# Sense.net
KiCad netlist of a schematic drawn in Altium Designer
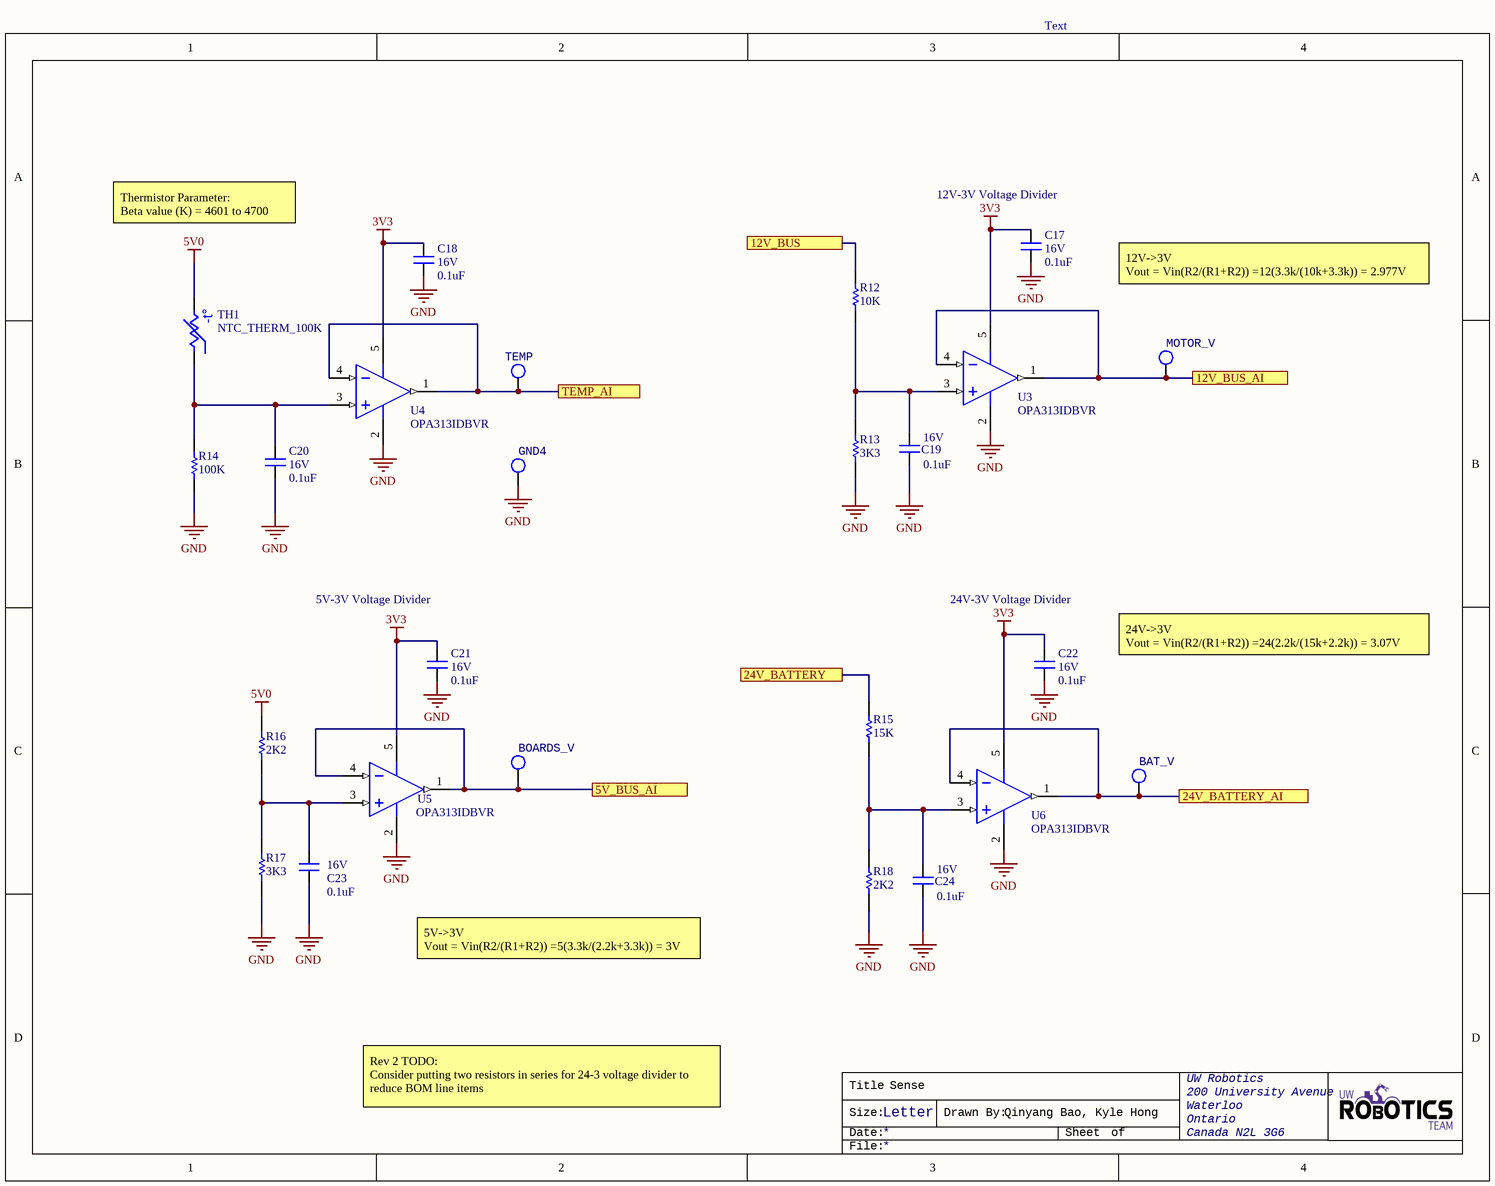
[diagram p0: Sense.SchDoc]

(export (version "E")
  (design (tool "Eeschema 10.0.6"))
  (components
    (comp (ref "BAT_V")
      (value "TESTPOINT_LOOP")
      (footprint "TESTPOINT_LOOP")
      (description "Loop testpoint through-hole pad")
      (fields (field (name "MANUFACTURER") "Keystone Electronics"))
      (libsource (lib "UWRT_Schematic_Library_2020") (part "TESTPOINT_LOOP"))
    )
    (comp (ref "BOARDS_V")
      (value "TESTPOINT_LOOP")
      (footprint "TESTPOINT_LOOP")
      (description "Loop testpoint through-hole pad")
      (fields (field (name "MANUFACTURER") "Keystone Electronics"))
      (libsource (lib "UWRT_Schematic_Library_2020") (part "TESTPOINT_LOOP"))
    )
    (comp (ref "C17")
      (value "0.1uF")
      (footprint "CAPC0603(1608)55_N")
      (description "CAP CER 0.1UF 16V X7R 0603")
      (fields
        (field (name "MPN") "CC0603KRX7R7BB104")
        (field (name "MANUFACTURER") "Yageo")
        (field (name "VOLTAGE RATING") "16V")
      )
      (libsource (lib "UWRT_Schematic_Library_2020") (part "CAP_0.1uF_16V_0603"))
    )
    (comp (ref "C18")
      (value "0.1uF")
      (footprint "CAPC0603(1608)55_N")
      (description "CAP CER 0.1UF 16V X7R 0603")
      (fields
        (field (name "MPN") "CC0603KRX7R7BB104")
        (field (name "MANUFACTURER") "Yageo")
        (field (name "VOLTAGE RATING") "16V")
      )
      (libsource (lib "UWRT_Schematic_Library_2020") (part "CAP_0.1uF_16V_0603"))
    )
    (comp (ref "C19")
      (value "0.1uF")
      (footprint "CAPC0603(1608)55_N")
      (description "CAP CER 0.1UF 16V X7R 0603")
      (fields
        (field (name "MPN") "CC0603KRX7R7BB104")
        (field (name "MANUFACTURER") "Yageo")
        (field (name "VOLTAGE RATING") "16V")
      )
      (libsource (lib "UWRT_Schematic_Library_2020") (part "CAP_0.1uF_16V_0603"))
    )
    (comp (ref "C20")
      (value "0.1uF")
      (footprint "CAPC0603(1608)55_N")
      (description "CAP CER 0.1UF 16V X7R 0603")
      (fields
        (field (name "MPN") "CC0603KRX7R7BB104")
        (field (name "MANUFACTURER") "Yageo")
        (field (name "VOLTAGE RATING") "16V")
      )
      (libsource (lib "UWRT_Schematic_Library_2020") (part "CAP_0.1uF_16V_0603"))
    )
    (comp (ref "C21")
      (value "0.1uF")
      (footprint "CAPC0603(1608)55_N")
      (description "CAP CER 0.1UF 16V X7R 0603")
      (fields
        (field (name "MPN") "CC0603KRX7R7BB104")
        (field (name "MANUFACTURER") "Yageo")
        (field (name "VOLTAGE RATING") "16V")
      )
      (libsource (lib "UWRT_Schematic_Library_2020") (part "CAP_0.1uF_16V_0603"))
    )
    (comp (ref "C22")
      (value "0.1uF")
      (footprint "CAPC0603(1608)55_N")
      (description "CAP CER 0.1UF 16V X7R 0603")
      (fields
        (field (name "MPN") "CC0603KRX7R7BB104")
        (field (name "MANUFACTURER") "Yageo")
        (field (name "VOLTAGE RATING") "16V")
      )
      (libsource (lib "UWRT_Schematic_Library_2020") (part "CAP_0.1uF_16V_0603"))
    )
    (comp (ref "C23")
      (value "0.1uF")
      (footprint "CAPC0603(1608)55_N")
      (description "CAP CER 0.1UF 16V X7R 0603")
      (fields
        (field (name "MPN") "CC0603KRX7R7BB104")
        (field (name "MANUFACTURER") "Yageo")
        (field (name "VOLTAGE RATING") "16V")
      )
      (libsource (lib "UWRT_Schematic_Library_2020") (part "CAP_0.1uF_16V_0603"))
    )
    (comp (ref "C24")
      (value "0.1uF")
      (footprint "CAPC0603(1608)55_N")
      (description "CAP CER 0.1UF 16V X7R 0603")
      (fields
        (field (name "MPN") "CC0603KRX7R7BB104")
        (field (name "MANUFACTURER") "Yageo")
        (field (name "VOLTAGE RATING") "16V")
      )
      (libsource (lib "UWRT_Schematic_Library_2020") (part "CAP_0.1uF_16V_0603"))
    )
    (comp (ref "GND4")
      (value "TESTPOINT_LOOP")
      (footprint "TESTPOINT_LOOP")
      (description "Loop testpoint through-hole pad")
      (fields (field (name "MANUFACTURER") "Keystone Electronics"))
      (libsource (lib "UWRT_Schematic_Library_2020") (part "TESTPOINT_LOOP"))
    )
    (comp (ref "MOTOR_V")
      (value "TESTPOINT_LOOP")
      (footprint "TESTPOINT_LOOP")
      (description "Loop testpoint through-hole pad")
      (fields (field (name "MANUFACTURER") "Keystone Electronics"))
      (libsource (lib "UWRT_Schematic_Library_2020") (part "TESTPOINT_LOOP"))
    )
    (comp (ref "R12")
      (value "10K")
      (footprint "RESC0603(1608)_N")
      (description "RES SMD 10K OHM 5% 1/10W 0603")
      (fields (field (name "TOLERANCE") "5%") (field (name "MANUFACTURER") "Yageo"))
      (libsource (lib "UWRT_Schematic_Library_2020") (part "RES_10K_0603"))
    )
    (comp (ref "R13")
      (value "3K3")
      (footprint "RESC0603(1608)_N")
      (description "RES SMD 3.3K OHM 5% 1/10W 0603")
      (fields (field (name "TOLERANCE") "5%") (field (name "MANUFACTURER") "Yageo"))
      (libsource (lib "UWRT_Schematic_Library_2020") (part "RES_3K3_0603"))
    )
    (comp (ref "R14")
      (value "100K")
      (footprint "RESC0603(1608)_N")
      (description "RES SMD 100K OHM 5% 1/10W 0603")
      (fields (field (name "TOLERANCE") "5%") (field (name "MANUFACTURER") "Yageo"))
      (libsource (lib "UWRT_Schematic_Library_2020") (part "RES_100K_0603"))
    )
    (comp (ref "R15")
      (value "15K")
      (footprint "RESC0603(1608)_N")
      (description "RES SMD 15K OHM 5% 1/10W 0603")
      (fields (field (name "TOLERANCE") "5%") (field (name "Comment") "RES_15K_0603"))
      (libsource (lib "UWRT_Schematic_Library_2020") (part "RES_15K_0603"))
    )
    (comp (ref "R16")
      (value "2K2")
      (footprint "RESC0603(1608)_N")
      (description "RES SMD 2.2K OHM 1% 1/10W 0603")
      (fields (field (name "TOLERANCE") "1%") (field (name "MANUFACTURER") "Yageo"))
      (libsource (lib "UWRT_Schematic_Library_2020") (part "RES_2K2_0603"))
    )
    (comp (ref "R17")
      (value "3K3")
      (footprint "RESC0603(1608)_N")
      (description "RES SMD 3.3K OHM 5% 1/10W 0603")
      (fields (field (name "TOLERANCE") "5%") (field (name "MANUFACTURER") "Yageo"))
      (libsource (lib "UWRT_Schematic_Library_2020") (part "RES_3K3_0603"))
    )
    (comp (ref "R18")
      (value "2K2")
      (footprint "RESC0603(1608)_N")
      (description "RES SMD 2.2K OHM 1% 1/10W 0603")
      (fields (field (name "TOLERANCE") "1%") (field (name "MANUFACTURER") "Yageo"))
      (libsource (lib "UWRT_Schematic_Library_2020") (part "RES_2K2_0603"))
    )
    (comp (ref "TEMP")
      (value "TESTPOINT_LOOP")
      (footprint "TESTPOINT_LOOP")
      (description "Loop testpoint through-hole pad")
      (fields (field (name "MANUFACTURER") "Keystone Electronics"))
      (libsource (lib "UWRT_Schematic_Library_2020") (part "TESTPOINT_LOOP"))
    )
    (comp (ref "TH1")
      (value "NTC_THERM_100K")
      (footprint "RESC0603(1608)_N")
      (description "THERM NTC 100KOHM 4700K 0603")
      (fields (field (name "MPN") "ERT-J1VV104J") (field (name "MANUFACTURER") "Panasonic"))
      (libsource (lib "UWRT_Schematic_Library_2020") (part "NTC_THERM_100K"))
    )
    (comp (ref "U3")
      (value "OPA313IDBVR")
      (footprint "DBV0005A_M")
      (description "IC OPAMP GP 1 CIRCUIT SOT23-5")
      (fields (field (name "MANUFACTURER") "Texas Instruments"))
      (libsource (lib "UWRT_Schematic_Library_2020") (part "OPAMP"))
    )
    (comp (ref "U4")
      (value "OPA313IDBVR")
      (footprint "DBV0005A_M")
      (description "IC OPAMP GP 1 CIRCUIT SOT23-5")
      (fields (field (name "MANUFACTURER") "Texas Instruments"))
      (libsource (lib "UWRT_Schematic_Library_2020") (part "OPAMP"))
    )
    (comp (ref "U5")
      (value "OPA313IDBVR")
      (footprint "DBV0005A_M")
      (description "IC OPAMP GP 1 CIRCUIT SOT23-5")
      (fields (field (name "MANUFACTURER") "Texas Instruments"))
      (libsource (lib "UWRT_Schematic_Library_2020") (part "OPAMP"))
    )
    (comp (ref "U6")
      (value "OPA313IDBVR")
      (footprint "DBV0005A_M")
      (description "IC OPAMP GP 1 CIRCUIT SOT23-5")
      (fields (field (name "MANUFACTURER") "Texas Instruments"))
      (libsource (lib "UWRT_Schematic_Library_2020") (part "OPAMP"))
    )
  )
  (nets
    (net (code "1") (name "/5V_BUS_AI") (class "Default")
      (node (ref "BOARDS_V") (pin "1") (pintype "passive"))
      (node (ref "U5") (pin "1") (pinfunction "OUT_1") (pintype "output"))
      (node (ref "U5") (pin "4") (pinfunction "IN-_4") (pintype "input"))
    )
    (net (code "2") (name "/12V_BUS") (class "Default")
      (node (ref "R12") (pin "2") (pinfunction "2_2") (pintype "passive"))
    )
    (net (code "3") (name "/12V_BUS_AI") (class "Default")
      (node (ref "MOTOR_V") (pin "1") (pintype "passive"))
      (node (ref "U3") (pin "1") (pinfunction "OUT_1") (pintype "output"))
      (node (ref "U3") (pin "4") (pinfunction "IN-_4") (pintype "input"))
    )
    (net (code "4") (name "/24V_BATTERY") (class "Default")
      (node (ref "R15") (pin "2") (pinfunction "2_2") (pintype "passive"))
    )
    (net (code "5") (name "/24V_BATTERY_AI") (class "Default")
      (node (ref "BAT_V") (pin "1") (pintype "passive"))
      (node (ref "U6") (pin "1") (pinfunction "OUT_1") (pintype "output"))
      (node (ref "U6") (pin "4") (pinfunction "IN-_4") (pintype "input"))
    )
    (net (code "6") (name "/TEMP_AI") (class "Default")
      (node (ref "TEMP") (pin "1") (pintype "passive"))
      (node (ref "U4") (pin "1") (pinfunction "OUT_1") (pintype "output"))
      (node (ref "U4") (pin "4") (pinfunction "IN-_4") (pintype "input"))
    )
    (net (code "7") (name "3V3") (class "Default")
      (node (ref "C17") (pin "2") (pinfunction "2_2") (pintype "passive"))
      (node (ref "C18") (pin "1") (pinfunction "1_1") (pintype "passive"))
      (node (ref "C21") (pin "2") (pinfunction "2_2") (pintype "passive"))
      (node (ref "C22") (pin "2") (pinfunction "2_2") (pintype "passive"))
      (node (ref "U3") (pin "5") (pinfunction "V+_5") (pintype "power_in"))
      (node (ref "U4") (pin "5") (pinfunction "V+_5") (pintype "power_in"))
      (node (ref "U5") (pin "5") (pinfunction "V+_5") (pintype "power_in"))
      (node (ref "U6") (pin "5") (pinfunction "V+_5") (pintype "power_in"))
    )
    (net (code "8") (name "5V0") (class "Default")
      (node (ref "R16") (pin "2") (pinfunction "2_2") (pintype "passive"))
      (node (ref "TH1") (pin "1") (pinfunction "1_1") (pintype "passive"))
    )
    (net (code "9") (name "GND") (class "Default")
      (node (ref "C17") (pin "1") (pinfunction "1_1") (pintype "passive"))
      (node (ref "C18") (pin "2") (pinfunction "2_2") (pintype "passive"))
      (node (ref "C19") (pin "1") (pinfunction "1_1") (pintype "passive"))
      (node (ref "C20") (pin "1") (pinfunction "1_1") (pintype "passive"))
      (node (ref "C21") (pin "1") (pinfunction "1_1") (pintype "passive"))
      (node (ref "C22") (pin "1") (pinfunction "1_1") (pintype "passive"))
      (node (ref "C23") (pin "1") (pinfunction "1_1") (pintype "passive"))
      (node (ref "C24") (pin "1") (pinfunction "1_1") (pintype "passive"))
      (node (ref "GND4") (pin "1") (pintype "passive"))
      (node (ref "R13") (pin "1") (pinfunction "1_1") (pintype "passive"))
      (node (ref "R14") (pin "1") (pinfunction "1_1") (pintype "passive"))
      (node (ref "R17") (pin "1") (pinfunction "1_1") (pintype "passive"))
      (node (ref "R18") (pin "1") (pinfunction "1_1") (pintype "passive"))
      (node (ref "U3") (pin "2") (pinfunction "V-_2") (pintype "power_in"))
      (node (ref "U4") (pin "2") (pinfunction "V-_2") (pintype "power_in"))
      (node (ref "U5") (pin "2") (pinfunction "V-_2") (pintype "power_in"))
      (node (ref "U6") (pin "2") (pinfunction "V-_2") (pintype "power_in"))
    )
    (net (code "10") (name "Net-(U3-IN+)") (class "Default")
      (node (ref "C19") (pin "2") (pinfunction "2_2") (pintype "passive"))
      (node (ref "R12") (pin "1") (pinfunction "1_1") (pintype "passive"))
      (node (ref "R13") (pin "2") (pinfunction "2_2") (pintype "passive"))
      (node (ref "U3") (pin "3") (pinfunction "IN+_3") (pintype "input"))
    )
    (net (code "11") (name "Net-(U4-IN+)") (class "Default")
      (node (ref "C20") (pin "2") (pinfunction "2_2") (pintype "passive"))
      (node (ref "R14") (pin "2") (pinfunction "2_2") (pintype "passive"))
      (node (ref "TH1") (pin "2") (pinfunction "2_2") (pintype "passive"))
      (node (ref "U4") (pin "3") (pinfunction "IN+_3") (pintype "input"))
    )
    (net (code "12") (name "Net-(U5-IN+)") (class "Default")
      (node (ref "C23") (pin "2") (pinfunction "2_2") (pintype "passive"))
      (node (ref "R16") (pin "1") (pinfunction "1_1") (pintype "passive"))
      (node (ref "R17") (pin "2") (pinfunction "2_2") (pintype "passive"))
      (node (ref "U5") (pin "3") (pinfunction "IN+_3") (pintype "input"))
    )
    (net (code "13") (name "Net-(U6-IN+)") (class "Default")
      (node (ref "C24") (pin "2") (pinfunction "2_2") (pintype "passive"))
      (node (ref "R15") (pin "1") (pinfunction "1_1") (pintype "passive"))
      (node (ref "R18") (pin "2") (pinfunction "2_2") (pintype "passive"))
      (node (ref "U6") (pin "3") (pinfunction "IN+_3") (pintype "input"))
    )
  )
)
